# pc2_key.net
KiCad netlist of a schematic drawn in EAGLE
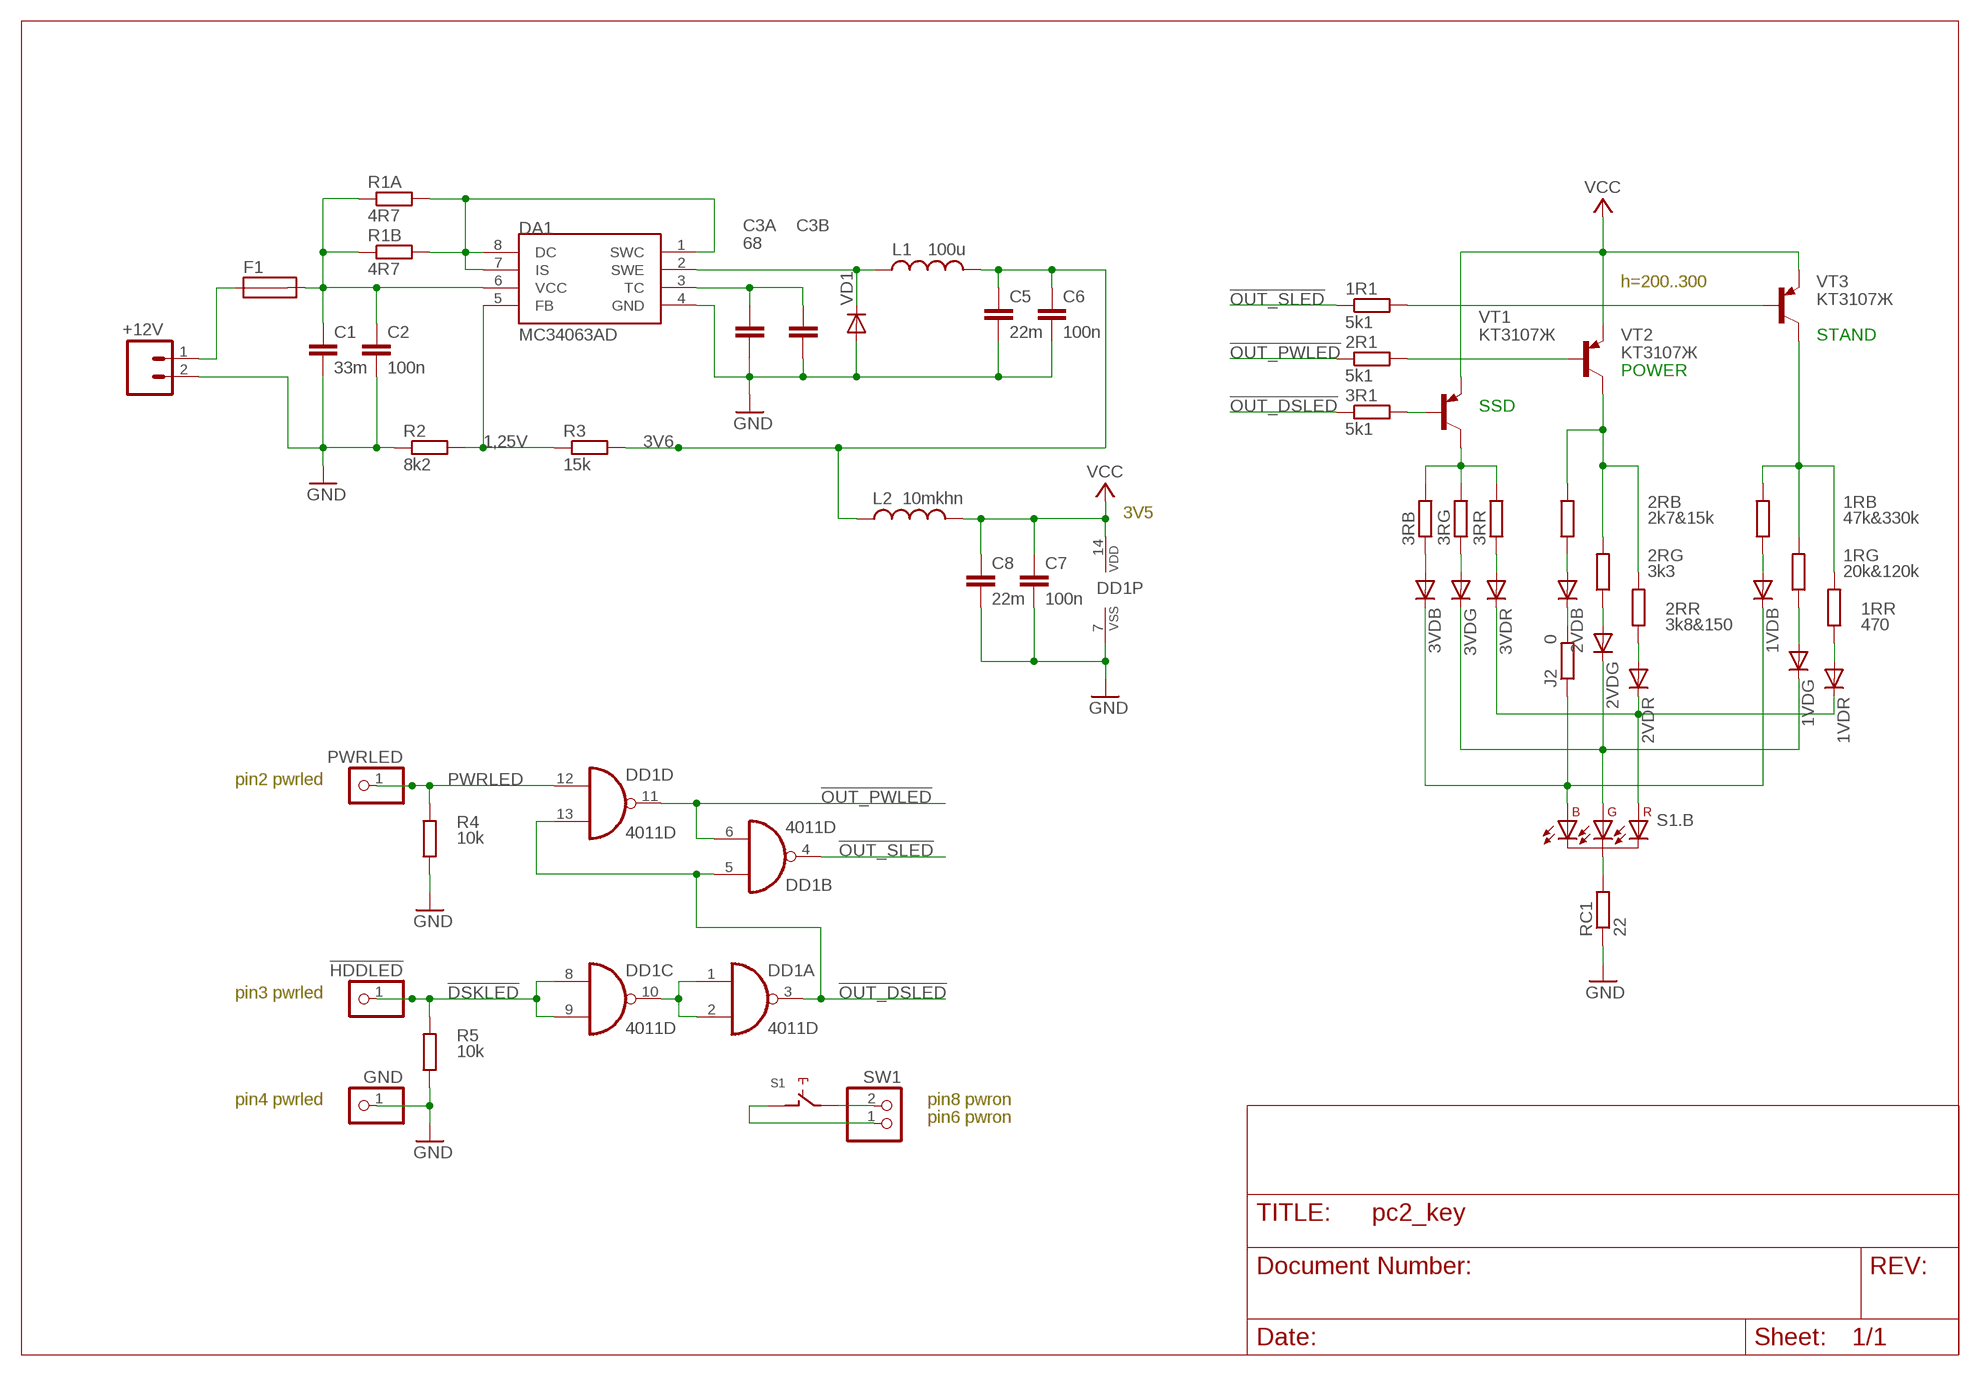
[diagram p0: schematic, sheet 1]

(export (version "E")
  (design (tool "Eeschema 10.0.6"))
  (components
    (comp (ref "!HDDLED")
      (value "PINHD-1X1")
      (footprint "eagle-import:1X01")
      (libsource (lib "eagle-import") (part "PINHD-1X1"))
    )
    (comp (ref "+12V")
      (value "CON_2P")
      (footprint "eagle-import:CON_PWR_2PIN4MM")
      (libsource (lib "eagle-import") (part "CON_2P"))
    )
    (comp (ref "1R1")
      (value "5k1")
      (footprint "eagle-import:R1206W")
      (libsource (lib "eagle-import") (part "R-EU_R1206W"))
    )
    (comp (ref "1RB")
      (value "47k&330k")
      (footprint "eagle-import:R0805")
      (libsource (lib "eagle-import") (part "R-EU_R0805"))
    )
    (comp (ref "1RG")
      (value "20k&120k")
      (footprint "eagle-import:R0805")
      (libsource (lib "eagle-import") (part "R-EU_R0805"))
    )
    (comp (ref "1RR")
      (value "470")
      (footprint "eagle-import:R0805")
      (libsource (lib "eagle-import") (part "R-EU_R0805"))
    )
    (comp (ref "1VDB")
      (value "DIODE-SOD80C")
      (footprint "eagle-import:SOD80C")
      (libsource (lib "eagle-import") (part "DIODE-SOD80C"))
    )
    (comp (ref "1VDG")
      (value "DIODE-SOD80C")
      (footprint "eagle-import:SOD80C")
      (libsource (lib "eagle-import") (part "DIODE-SOD80C"))
    )
    (comp (ref "1VDR")
      (value "DIODE-SOD80C")
      (footprint "eagle-import:SOD80C")
      (libsource (lib "eagle-import") (part "DIODE-SOD80C"))
    )
    (comp (ref "2R1")
      (value "5k1")
      (footprint "eagle-import:R1206W")
      (libsource (lib "eagle-import") (part "R-EU_R1206W"))
    )
    (comp (ref "2RB")
      (value "2k7&15k")
      (footprint "eagle-import:R0805")
      (libsource (lib "eagle-import") (part "R-EU_R0805"))
    )
    (comp (ref "2RG")
      (value "3k3")
      (footprint "eagle-import:R0805")
      (libsource (lib "eagle-import") (part "R-EU_R0805"))
    )
    (comp (ref "2RR")
      (value "3k8&150")
      (footprint "eagle-import:R0805")
      (libsource (lib "eagle-import") (part "R-EU_R0805"))
    )
    (comp (ref "2VDB")
      (value "DIODE-SOD80C")
      (footprint "eagle-import:SOD80C")
      (libsource (lib "eagle-import") (part "DIODE-SOD80C"))
    )
    (comp (ref "2VDG")
      (value "DIODE-SOD80C")
      (footprint "eagle-import:SOD80C")
      (libsource (lib "eagle-import") (part "DIODE-SOD80C"))
    )
    (comp (ref "2VDR")
      (value "DIODE-SOD80C")
      (footprint "eagle-import:SOD80C")
      (libsource (lib "eagle-import") (part "DIODE-SOD80C"))
    )
    (comp (ref "3R1")
      (value "5k1")
      (footprint "eagle-import:R1206W")
      (libsource (lib "eagle-import") (part "R-EU_R1206W"))
    )
    (comp (ref "3RB")
      (value "R-EU_R0805")
      (footprint "eagle-import:R0805")
      (libsource (lib "eagle-import") (part "R-EU_R0805"))
    )
    (comp (ref "3RG")
      (value "R-EU_R0805")
      (footprint "eagle-import:R0805")
      (libsource (lib "eagle-import") (part "R-EU_R0805"))
    )
    (comp (ref "3RR")
      (value "R-EU_R0805")
      (footprint "eagle-import:R0805")
      (libsource (lib "eagle-import") (part "R-EU_R0805"))
    )
    (comp (ref "3VDB")
      (value "DIODE-SOD80C")
      (footprint "eagle-import:SOD80C")
      (libsource (lib "eagle-import") (part "DIODE-SOD80C"))
    )
    (comp (ref "3VDG")
      (value "DIODE-SOD80C")
      (footprint "eagle-import:SOD80C")
      (libsource (lib "eagle-import") (part "DIODE-SOD80C"))
    )
    (comp (ref "3VDR")
      (value "DIODE-SOD80C")
      (footprint "eagle-import:SOD80C")
      (libsource (lib "eagle-import") (part "DIODE-SOD80C"))
    )
    (comp (ref "C1")
      (value "33m")
      (footprint "eagle-import:C1210")
      (libsource (lib "eagle-import") (part "C-EUC1210"))
    )
    (comp (ref "C2")
      (value "100n")
      (footprint "eagle-import:C0805K")
      (libsource (lib "eagle-import") (part "resistor_C-EUC0805K"))
    )
    (comp (ref "C3A")
      (value "68")
      (footprint "eagle-import:C0805K")
      (libsource (lib "eagle-import") (part "resistor_C-EUC0805K"))
    )
    (comp (ref "C3B")
      (value "C-EUC0805K")
      (footprint "eagle-import:C0805K")
      (libsource (lib "eagle-import") (part "resistor_C-EUC0805K"))
    )
    (comp (ref "C5")
      (value "22m")
      (footprint "eagle-import:C1210")
      (libsource (lib "eagle-import") (part "C-EUC1210"))
    )
    (comp (ref "C6")
      (value "100n")
      (footprint "eagle-import:C0805K")
      (libsource (lib "eagle-import") (part "resistor_C-EUC0805K"))
    )
    (comp (ref "C7")
      (value "100n")
      (footprint "eagle-import:C0805K")
      (libsource (lib "eagle-import") (part "resistor_C-EUC0805K"))
    )
    (comp (ref "C8")
      (value "22m")
      (footprint "eagle-import:C1210")
      (libsource (lib "eagle-import") (part "C-EUC1210"))
    )
    (comp (ref "DA1")
      (value "MC34063AD")
      (footprint "eagle-import:SOIC8")
      (libsource (lib "eagle-import") (part "MC34063AD"))
    )
    (comp (ref "DD1")
      (value "4011D")
      (footprint "eagle-import:SO14")
      (libsource (lib "eagle-import") (part "4011D"))
    )
    (comp (ref "F1")
      (value "SH32")
      (footprint "eagle-import:SH32")
      (fields (field (name "MPN") "10207101009"))
      (libsource (lib "eagle-import") (part "SH32"))
    )
    (comp (ref "GND")
      (value "PINHD-1X1")
      (footprint "eagle-import:1X01")
      (libsource (lib "eagle-import") (part "PINHD-1X1"))
    )
    (comp (ref "J2")
      (value "0")
      (footprint "eagle-import:R1206W")
      (libsource (lib "eagle-import") (part "R-EU_R1206W"))
    )
    (comp (ref "L1")
      (value "100u")
      (footprint "eagle-import:LH7X10MM")
      (libsource (lib "eagle-import") (part "L_LH7X10MM"))
    )
    (comp (ref "L2")
      (value "10mkhn")
      (footprint "eagle-import:PIS2816")
      (libsource (lib "eagle-import") (part "L-USPIS2816"))
    )
    (comp (ref "PWRLED")
      (value "PINHD-1X1")
      (footprint "eagle-import:1X01")
      (libsource (lib "eagle-import") (part "PINHD-1X1"))
    )
    (comp (ref "R1A")
      (value "4R7")
      (footprint "eagle-import:R1206")
      (libsource (lib "eagle-import") (part "resistor_R-EU_R1206"))
    )
    (comp (ref "R1B")
      (value "4R7")
      (footprint "eagle-import:R1206")
      (libsource (lib "eagle-import") (part "resistor_R-EU_R1206"))
    )
    (comp (ref "R2")
      (value "8k2")
      (footprint "eagle-import:R0805")
      (libsource (lib "eagle-import") (part "resistor_R-EU_R0805"))
    )
    (comp (ref "R3")
      (value "15k")
      (footprint "eagle-import:R0805")
      (libsource (lib "eagle-import") (part "resistor_R-EU_R0805"))
    )
    (comp (ref "R4")
      (value "10k")
      (footprint "eagle-import:M0805")
      (libsource (lib "eagle-import") (part "R-EU_M0805"))
    )
    (comp (ref "R5")
      (value "10k")
      (footprint "eagle-import:R1206W")
      (libsource (lib "eagle-import") (part "R-EU_R1206W"))
    )
    (comp (ref "RC1")
      (value "22")
      (footprint "eagle-import:R0805")
      (libsource (lib "eagle-import") (part "R-EU_R0805"))
    )
    (comp (ref "S1")
      (value "CHERRY-MX")
      (footprint "eagle-import:CHERRY-MX-4P")
      (libsource (lib "eagle-import") (part "CHERRY-MX"))
    )
    (comp (ref "SW1")
      (value "PINHD-1X2")
      (footprint "eagle-import:1X02")
      (libsource (lib "eagle-import") (part "PINHD-1X2"))
    )
    (comp (ref "VD1")
      (value "DIODE-SMB")
      (footprint "eagle-import:SMB")
      (libsource (lib "eagle-import") (part "DIODE-SMB"))
    )
    (comp (ref "VT1")
      (value "KT3107Ж")
      (footprint "eagle-import:TO92")
      (libsource (lib "eagle-import") (part "BJT_PNP_TO-92_EBC"))
    )
    (comp (ref "VT2")
      (value "KT3107Ж")
      (footprint "eagle-import:TO92")
      (libsource (lib "eagle-import") (part "BJT_PNP_TO-92_EBC"))
    )
    (comp (ref "VT3")
      (value "KT3107Ж")
      (footprint "eagle-import:TO92")
      (libsource (lib "eagle-import") (part "BJT_PNP_TO-92_EBC"))
    )
  )
  (nets
    (net (code "1") (name "/1,25V") (class "Default")
      (node (ref "DA1") (pin "5") (pinfunction "FB_5") (pintype "passive"))
      (node (ref "R2") (pin "2") (pinfunction "2_2") (pintype "passive"))
      (node (ref "R3") (pin "1") (pinfunction "1_1") (pintype "passive"))
    )
    (net (code "2") (name "/3V6") (class "Default")
      (node (ref "C5") (pin "1") (pinfunction "1_1") (pintype "passive"))
      (node (ref "C6") (pin "1") (pinfunction "1_1") (pintype "passive"))
      (node (ref "L1") (pin "1") (pinfunction "1_1") (pintype "passive"))
      (node (ref "L2") (pin "1") (pinfunction "1_1") (pintype "passive"))
      (node (ref "R3") (pin "2") (pinfunction "2_2") (pintype "passive"))
    )
    (net (code "3") (name "/PWRLED") (class "Default")
      (node (ref "DD1") (pin "12") (pinfunction "I0_12") (pintype "input"))
      (node (ref "PWRLED") (pin "1") (pinfunction "1_1") (pintype "passive"))
      (node (ref "R4") (pin "2") (pinfunction "2_2") (pintype "passive"))
    )
    (net (code "4") (name "/~{DSKLED}") (class "Default")
      (node (ref "!HDDLED") (pin "1") (pinfunction "1_1") (pintype "passive"))
      (node (ref "DD1") (pin "8") (pinfunction "I0_8") (pintype "input"))
      (node (ref "DD1") (pin "9") (pinfunction "I1_9") (pintype "input"))
      (node (ref "R5") (pin "2") (pinfunction "2_2") (pintype "passive"))
    )
    (net (code "5") (name "/~{OUT_DSLED}") (class "Default")
      (node (ref "3R1") (pin "1") (pinfunction "1_1") (pintype "passive"))
      (node (ref "DD1") (pin "13") (pinfunction "I1_13") (pintype "input"))
      (node (ref "DD1") (pin "3") (pinfunction "O_3") (pintype "output"))
      (node (ref "DD1") (pin "5") (pinfunction "I0_5") (pintype "input"))
    )
    (net (code "6") (name "/~{OUT_PWLED}") (class "Default")
      (node (ref "2R1") (pin "1") (pinfunction "1_1") (pintype "passive"))
      (node (ref "DD1") (pin "11") (pinfunction "O_11") (pintype "output"))
      (node (ref "DD1") (pin "6") (pinfunction "I1_6") (pintype "input"))
    )
    (net (code "7") (name "/~{OUT_SLED}") (class "Default")
      (node (ref "1R1") (pin "1") (pinfunction "1_1") (pintype "passive"))
      (node (ref "DD1") (pin "4") (pinfunction "O_4") (pintype "output"))
    )
    (net (code "8") (name "GND") (class "Default")
      (node (ref "+12V") (pin "2") (pinfunction "2_2") (pintype "passive"))
      (node (ref "C1") (pin "2") (pinfunction "2_2") (pintype "passive"))
      (node (ref "C2") (pin "2") (pinfunction "2_2") (pintype "passive"))
      (node (ref "C3A") (pin "2") (pinfunction "2_2") (pintype "passive"))
      (node (ref "C3B") (pin "2") (pinfunction "2_2") (pintype "passive"))
      (node (ref "C5") (pin "2") (pinfunction "2_2") (pintype "passive"))
      (node (ref "C6") (pin "2") (pinfunction "2_2") (pintype "passive"))
      (node (ref "C7") (pin "2") (pinfunction "2_2") (pintype "passive"))
      (node (ref "C8") (pin "2") (pinfunction "2_2") (pintype "passive"))
      (node (ref "DA1") (pin "4") (pinfunction "GND_4") (pintype "passive"))
      (node (ref "DD1") (pin "7") (pinfunction "VSS_7") (pintype "power_in"))
      (node (ref "GND") (pin "1") (pinfunction "1_1") (pintype "passive"))
      (node (ref "R2") (pin "1") (pinfunction "1_1") (pintype "passive"))
      (node (ref "R4") (pin "1") (pinfunction "1_1") (pintype "passive"))
      (node (ref "R5") (pin "1") (pinfunction "1_1") (pintype "passive"))
      (node (ref "RC1") (pin "1") (pinfunction "1_1") (pintype "passive"))
      (node (ref "VD1") (pin "A") (pinfunction "A_A") (pintype "passive"))
    )
    (net (code "9") (name "Net-(1RB-Pad1)") (class "Default")
      (node (ref "1RB") (pin "1") (pinfunction "1_1") (pintype "passive"))
      (node (ref "1VDB") (pin "A") (pinfunction "A_A") (pintype "passive"))
    )
    (net (code "10") (name "Net-(1RG-Pad1)") (class "Default")
      (node (ref "1RG") (pin "1") (pinfunction "1_1") (pintype "passive"))
      (node (ref "1VDG") (pin "A") (pinfunction "A_A") (pintype "passive"))
    )
    (net (code "11") (name "Net-(1RR-Pad1)") (class "Default")
      (node (ref "1RR") (pin "1") (pinfunction "1_1") (pintype "passive"))
      (node (ref "1VDR") (pin "A") (pinfunction "A_A") (pintype "passive"))
    )
    (net (code "12") (name "Net-(2RB-Pad1)") (class "Default")
      (node (ref "2RB") (pin "1") (pinfunction "1_1") (pintype "passive"))
      (node (ref "2VDB") (pin "A") (pinfunction "A_A") (pintype "passive"))
    )
    (net (code "13") (name "Net-(2RG-Pad1)") (class "Default")
      (node (ref "2RG") (pin "1") (pinfunction "1_1") (pintype "passive"))
      (node (ref "2VDG") (pin "A") (pinfunction "A_A") (pintype "passive"))
    )
    (net (code "14") (name "Net-(2RR-Pad1)") (class "Default")
      (node (ref "2RR") (pin "1") (pinfunction "1_1") (pintype "passive"))
      (node (ref "2VDR") (pin "A") (pinfunction "A_A") (pintype "passive"))
    )
    (net (code "15") (name "Net-(2VDB-PadC)") (class "Default")
      (node (ref "2VDB") (pin "C") (pinfunction "C_C") (pintype "passive"))
      (node (ref "J2") (pin "2") (pinfunction "2_2") (pintype "passive"))
    )
    (net (code "16") (name "Net-(3RB-Pad1)") (class "Default")
      (node (ref "3RB") (pin "1") (pinfunction "1_1") (pintype "passive"))
      (node (ref "3VDB") (pin "A") (pinfunction "A_A") (pintype "passive"))
    )
    (net (code "17") (name "Net-(3RG-Pad1)") (class "Default")
      (node (ref "3RG") (pin "1") (pinfunction "1_1") (pintype "passive"))
      (node (ref "3VDG") (pin "A") (pinfunction "A_A") (pintype "passive"))
    )
    (net (code "18") (name "Net-(3RR-Pad1)") (class "Default")
      (node (ref "3RR") (pin "1") (pinfunction "1_1") (pintype "passive"))
      (node (ref "3VDR") (pin "A") (pinfunction "A_A") (pintype "passive"))
    )
    (net (code "19") (name "Net-(DA1-DC)") (class "Default")
      (node (ref "DA1") (pin "1") (pinfunction "SWC_1") (pintype "passive"))
      (node (ref "DA1") (pin "7") (pinfunction "IS_7") (pintype "passive"))
      (node (ref "DA1") (pin "8") (pinfunction "DC_8") (pintype "passive"))
      (node (ref "R1A") (pin "2") (pinfunction "2_2") (pintype "passive"))
      (node (ref "R1B") (pin "2") (pinfunction "2_2") (pintype "passive"))
    )
    (net (code "20") (name "Net-(DA1-SWE)") (class "Default")
      (node (ref "DA1") (pin "2") (pinfunction "SWE_2") (pintype "passive"))
      (node (ref "L1") (pin "2") (pinfunction "2_2") (pintype "passive"))
      (node (ref "VD1") (pin "C") (pinfunction "C_C") (pintype "passive"))
    )
    (net (code "21") (name "Net-(DA1-TC)") (class "Default")
      (node (ref "C3A") (pin "1") (pinfunction "1_1") (pintype "passive"))
      (node (ref "C3B") (pin "1") (pinfunction "1_1") (pintype "passive"))
      (node (ref "DA1") (pin "3") (pinfunction "TC_3") (pintype "passive"))
    )
    (net (code "22") (name "Net-(DA1-VCC)") (class "Default")
      (node (ref "C1") (pin "1") (pinfunction "1_1") (pintype "passive"))
      (node (ref "C2") (pin "1") (pinfunction "1_1") (pintype "passive"))
      (node (ref "DA1") (pin "6") (pinfunction "VCC_6") (pintype "passive"))
      (node (ref "F1") (pin "P$2") (pinfunction "2A_P$2") (pintype "passive"))
      (node (ref "R1A") (pin "1") (pinfunction "1_1") (pintype "passive"))
      (node (ref "R1B") (pin "1") (pinfunction "1_1") (pintype "passive"))
    )
    (net (code "23") (name "Net-(DD1A-I0)") (class "Default")
      (node (ref "DD1") (pin "1") (pinfunction "I0_1") (pintype "input"))
      (node (ref "DD1") (pin "10") (pinfunction "O_10") (pintype "output"))
      (node (ref "DD1") (pin "2") (pinfunction "I1_2") (pintype "input"))
    )
    (net (code "24") (name "Net-(F1-1A)") (class "Default")
      (node (ref "+12V") (pin "1") (pinfunction "1_1") (pintype "passive"))
      (node (ref "F1") (pin "P$1") (pinfunction "1A_P$1") (pintype "passive"))
    )
    (net (code "25") (name "Net-(S1-PadSW1)") (class "Default")
      (node (ref "S1") (pin "SW1") (pinfunction "SW1_SW1") (pintype "passive"))
      (node (ref "SW1") (pin "2") (pinfunction "2_2") (pintype "passive"))
    )
    (net (code "26") (name "Net-(S1-PadSW2)") (class "Default")
      (node (ref "S1") (pin "SW2") (pinfunction "SW2_SW2") (pintype "passive"))
      (node (ref "SW1") (pin "1") (pinfunction "1_1") (pintype "passive"))
    )
    (net (code "27") (name "Net-(S1B-B)") (class "Default")
      (node (ref "1VDB") (pin "C") (pinfunction "C_C") (pintype "passive"))
      (node (ref "3VDB") (pin "C") (pinfunction "C_C") (pintype "passive"))
      (node (ref "J2") (pin "1") (pinfunction "1_1") (pintype "passive"))
      (node (ref "S1") (pin "D1") (pinfunction "B_D1") (pintype "passive"))
    )
    (net (code "28") (name "Net-(S1B-G)") (class "Default")
      (node (ref "1VDG") (pin "C") (pinfunction "C_C") (pintype "passive"))
      (node (ref "2VDG") (pin "C") (pinfunction "C_C") (pintype "passive"))
      (node (ref "3VDG") (pin "C") (pinfunction "C_C") (pintype "passive"))
      (node (ref "S1") (pin "D2") (pinfunction "G_D2") (pintype "passive"))
    )
    (net (code "29") (name "Net-(S1B-R)") (class "Default")
      (node (ref "1VDR") (pin "C") (pinfunction "C_C") (pintype "passive"))
      (node (ref "2VDR") (pin "C") (pinfunction "C_C") (pintype "passive"))
      (node (ref "3VDR") (pin "C") (pinfunction "C_C") (pintype "passive"))
      (node (ref "S1") (pin "D4") (pinfunction "R_D4") (pintype "passive"))
    )
    (net (code "30") (name "Net-(S1B-RGB-)") (class "Default")
      (node (ref "RC1") (pin "2") (pinfunction "2_2") (pintype "passive"))
      (node (ref "S1") (pin "D3") (pinfunction "RGB-_D3") (pintype "bidirectional"))
    )
    (net (code "31") (name "Net-(VT1-B)") (class "Default")
      (node (ref "3R1") (pin "2") (pinfunction "2_2") (pintype "passive"))
      (node (ref "VT1") (pin "2") (pinfunction "B_2") (pintype "passive"))
    )
    (net (code "32") (name "Net-(VT1-C)") (class "Default")
      (node (ref "3RB") (pin "2") (pinfunction "2_2") (pintype "passive"))
      (node (ref "3RG") (pin "2") (pinfunction "2_2") (pintype "passive"))
      (node (ref "3RR") (pin "2") (pinfunction "2_2") (pintype "passive"))
      (node (ref "VT1") (pin "3") (pinfunction "C_3") (pintype "passive"))
    )
    (net (code "33") (name "Net-(VT2-B)") (class "Default")
      (node (ref "2R1") (pin "2") (pinfunction "2_2") (pintype "passive"))
      (node (ref "VT2") (pin "2") (pinfunction "B_2") (pintype "passive"))
    )
    (net (code "34") (name "Net-(VT2-C)") (class "Default")
      (node (ref "2RB") (pin "2") (pinfunction "2_2") (pintype "passive"))
      (node (ref "2RG") (pin "2") (pinfunction "2_2") (pintype "passive"))
      (node (ref "2RR") (pin "2") (pinfunction "2_2") (pintype "passive"))
      (node (ref "VT2") (pin "3") (pinfunction "C_3") (pintype "passive"))
    )
    (net (code "35") (name "Net-(VT3-B)") (class "Default")
      (node (ref "1R1") (pin "2") (pinfunction "2_2") (pintype "passive"))
      (node (ref "VT3") (pin "2") (pinfunction "B_2") (pintype "passive"))
    )
    (net (code "36") (name "Net-(VT3-C)") (class "Default")
      (node (ref "1RB") (pin "2") (pinfunction "2_2") (pintype "passive"))
      (node (ref "1RG") (pin "2") (pinfunction "2_2") (pintype "passive"))
      (node (ref "1RR") (pin "2") (pinfunction "2_2") (pintype "passive"))
      (node (ref "VT3") (pin "3") (pinfunction "C_3") (pintype "passive"))
    )
    (net (code "37") (name "VCC") (class "Default")
      (node (ref "C7") (pin "1") (pinfunction "1_1") (pintype "passive"))
      (node (ref "C8") (pin "1") (pinfunction "1_1") (pintype "passive"))
      (node (ref "DD1") (pin "14") (pinfunction "VDD_14") (pintype "power_in"))
      (node (ref "L2") (pin "2") (pinfunction "2_2") (pintype "passive"))
      (node (ref "VT1") (pin "1") (pinfunction "E_1") (pintype "passive"))
      (node (ref "VT2") (pin "1") (pinfunction "E_1") (pintype "passive"))
      (node (ref "VT3") (pin "1") (pinfunction "E_1") (pintype "passive"))
    )
  )
)
